# Sheet1.net
KiCad netlist of a schematic drawn in Altium Designer
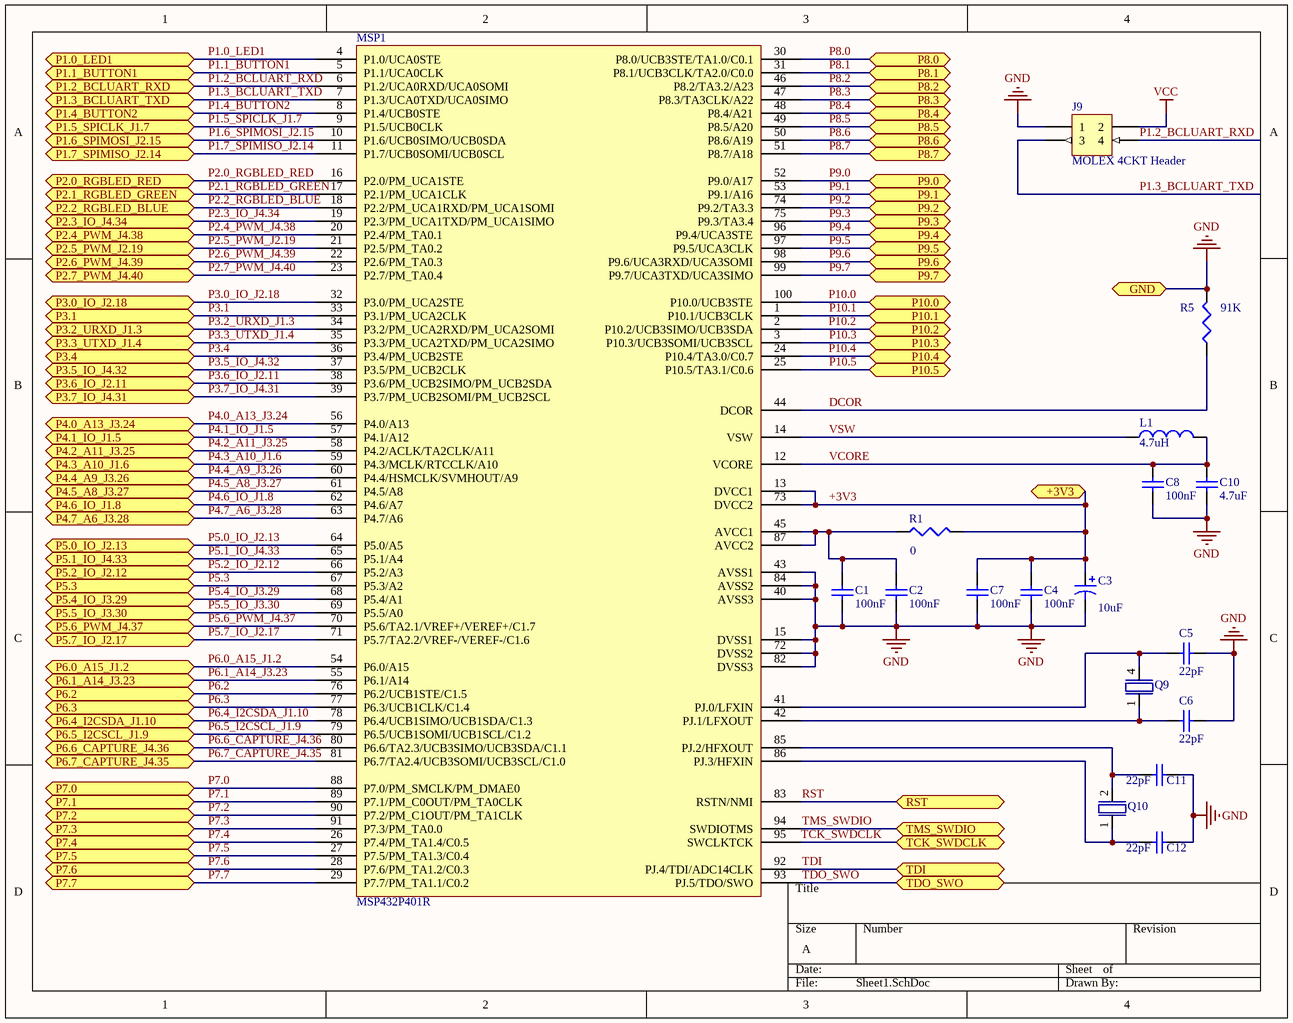
[diagram p0: Sheet1.SchDoc]

(export (version "E")
  (design (tool "Eeschema 10.0.6"))
  (components
    (comp (ref "C1")
      (value "100nF")
      (footprint "0402")
      (description "Capacitor (Semiconductor SIM Model)")
      (fields (field (name "Comment") "Cap Semi") (field (name "PUBLISHER") "Altium Limited"))
      (libsource (lib "Miscellaneous Devices") (part "Cap Semi"))
    )
    (comp (ref "C2")
      (value "100nF")
      (footprint "0402")
      (description "Capacitor (Semiconductor SIM Model)")
      (fields (field (name "Comment") "Cap Semi") (field (name "PUBLISHER") "Altium Limited"))
      (libsource (lib "Miscellaneous Devices") (part "Cap Semi"))
    )
    (comp (ref "C3")
      (value "10uF")
      (footprint "C0805")
      (description "Polarized Capacitor (Surface Mount)")
      (fields (field (name "Comment") "Cap Pol3") (field (name "PUBLISHER") "Altium Limited"))
      (libsource (lib "Miscellaneous Devices") (part "Cap Pol3"))
    )
    (comp (ref "C4")
      (value "100nF")
      (footprint "0402")
      (description "Capacitor (Semiconductor SIM Model)")
      (fields (field (name "Comment") "Cap Semi") (field (name "PUBLISHER") "Altium Limited"))
      (libsource (lib "Miscellaneous Devices") (part "Cap Semi"))
    )
    (comp (ref "C5")
      (value "22pF")
      (footprint "0402")
      (description "Capacitor (Semiconductor SIM Model)")
      (fields (field (name "Comment") "Cap Semi") (field (name "PUBLISHER") "Altium Limited"))
      (libsource (lib "Miscellaneous Devices") (part "Cap Semi"))
    )
    (comp (ref "C6")
      (value "22pF")
      (footprint "0402")
      (description "Capacitor (Semiconductor SIM Model)")
      (fields (field (name "Comment") "Cap Semi") (field (name "PUBLISHER") "Altium Limited"))
      (libsource (lib "Miscellaneous Devices") (part "Cap Semi"))
    )
    (comp (ref "C7")
      (value "100nF")
      (footprint "0402")
      (description "Capacitor (Semiconductor SIM Model)")
      (fields (field (name "Comment") "Cap Semi") (field (name "PUBLISHER") "Altium Limited"))
      (libsource (lib "Miscellaneous Devices") (part "Cap Semi"))
    )
    (comp (ref "C8")
      (value "100nF")
      (footprint "0402")
      (description "Capacitor (Semiconductor SIM Model)")
      (fields (field (name "Comment") "Cap Semi") (field (name "PUBLISHER") "Altium Limited"))
      (libsource (lib "Miscellaneous Devices") (part "Cap Semi"))
    )
    (comp (ref "C10")
      (value "4.7uF")
      (footprint "0402")
      (description "Capacitor (Semiconductor SIM Model)")
      (fields (field (name "Comment") "Cap Semi") (field (name "PUBLISHER") "Altium Limited"))
      (libsource (lib "Miscellaneous Devices") (part "Cap Semi"))
    )
    (comp (ref "C11")
      (value "22pF")
      (footprint "0402")
      (description "Capacitor (Semiconductor SIM Model)")
      (fields (field (name "Comment") "Cap Semi") (field (name "PUBLISHER") "Altium Limited"))
      (libsource (lib "Miscellaneous Devices") (part "Cap Semi"))
    )
    (comp (ref "C12")
      (value "22pF")
      (footprint "0402")
      (description "Capacitor (Semiconductor SIM Model)")
      (fields (field (name "Comment") "Cap Semi") (field (name "PUBLISHER") "Altium Limited"))
      (libsource (lib "Miscellaneous Devices") (part "Cap Semi"))
    )
    (comp (ref "J9")
      (value "MOLEX 4CKT Header")
      (footprint "MOLEX 4CKT Header")
      (libsource (lib "actuatorBoard") (part "MOLEX 4CKT Header"))
    )
    (comp (ref "L1")
      (value "4.7uH")
      (footprint "0402-A")
      (description "Inductor")
      (fields (field (name "PUBLISHER") "Altium Limited"))
      (libsource (lib "Miscellaneous Devices") (part "Inductor"))
    )
    (comp (ref "MSP1")
      (value "MSP432P401R")
      (footprint "MSP432P401R")
      (libsource (lib "actuatorBoard") (part "MSP432P401R"))
    )
    (comp (ref "Q9")
      (value "Crystal Oscillator")
      (footprint "4-SOJ")
      (libsource (lib "actuatorBoard") (part "Crystal Oscillator"))
    )
    (comp (ref "Q10")
      (value "Crystal Oscillator")
      (footprint "HC-49/US")
      (libsource (lib "") (part "Crystal Oscillator_1"))
    )
    (comp (ref "R1")
      (value "0")
      (footprint "J1-0603")
      (description "Resistor")
      (fields (field (name "Comment") "Res3") (field (name "PUBLISHER") "Altium Limited"))
      (libsource (lib "Miscellaneous Devices") (part "Res3"))
    )
    (comp (ref "R5")
      (value "91K")
      (footprint "J1-0603")
      (description "Resistor")
      (fields (field (name "Comment") "Res3") (field (name "PUBLISHER") "Altium Limited"))
      (libsource (lib "Miscellaneous Devices") (part "Res3"))
    )
  )
  (nets
    (net (code "1") (name "/+3V3") (class "Default")
      (node (ref "C3") (pin "1") (pinfunction "1_1") (pintype "passive"))
      (node (ref "C4") (pin "2") (pinfunction "2_2") (pintype "passive"))
      (node (ref "C7") (pin "2") (pinfunction "2_2") (pintype "passive"))
      (node (ref "MSP1") (pin "13") (pinfunction "DVCC1_13") (pintype "passive"))
      (node (ref "MSP1") (pin "73") (pinfunction "DVCC2_73") (pintype "passive"))
      (node (ref "R1") (pin "2") (pinfunction "2_2") (pintype "passive"))
    )
    (net (code "2") (name "/DCOR") (class "Default")
      (node (ref "MSP1") (pin "44") (pinfunction "DCOR_44") (pintype "passive"))
      (node (ref "R5") (pin "1") (pinfunction "1_1") (pintype "passive"))
    )
    (net (code "3") (name "/P1.0_LED1") (class "Default")
      (node (ref "MSP1") (pin "4") (pinfunction "P1.0/UCA0STE_4") (pintype "passive"))
    )
    (net (code "4") (name "/P1.1_BUTTON1") (class "Default")
      (node (ref "MSP1") (pin "5") (pinfunction "P1.1/UCA0CLK_5") (pintype "passive"))
    )
    (net (code "5") (name "/P1.2_BCLUART_RXD") (class "Default")
      (node (ref "J9") (pin "4") (pinfunction "4_4") (pintype "input"))
      (node (ref "MSP1") (pin "6") (pinfunction "P1.2/UCA0RXD/UCA0SOMI_6") (pintype "passive"))
    )
    (net (code "6") (name "/P1.3_BCLUART_TXD") (class "Default")
      (node (ref "J9") (pin "3") (pinfunction "3_3") (pintype "output"))
      (node (ref "MSP1") (pin "7") (pinfunction "P1.3/UCA0TXD/UCA0SIMO_7") (pintype "passive"))
    )
    (net (code "7") (name "/P1.4_BUTTON2") (class "Default")
      (node (ref "MSP1") (pin "8") (pinfunction "P1.4/UCB0STE_8") (pintype "passive"))
    )
    (net (code "8") (name "/P1.5_SPICLK_J1.7") (class "Default")
      (node (ref "MSP1") (pin "9") (pinfunction "P1.5/UCB0CLK_9") (pintype "passive"))
    )
    (net (code "9") (name "/P1.6_SPIMOSI_J2.15") (class "Default")
      (node (ref "MSP1") (pin "10") (pinfunction "P1.6/UCB0SIMO/UCB0SDA_10") (pintype "passive"))
    )
    (net (code "10") (name "/P1.7_SPIMISO_J2.14") (class "Default")
      (node (ref "MSP1") (pin "11") (pinfunction "P1.7/UCB0SOMI/UCB0SCL_11") (pintype "passive"))
    )
    (net (code "11") (name "/P2.0_RGBLED_RED") (class "Default")
      (node (ref "MSP1") (pin "16") (pinfunction "P2.0/PM_UCA1STE_16") (pintype "passive"))
    )
    (net (code "12") (name "/P2.1_RGBLED_GREEN") (class "Default")
      (node (ref "MSP1") (pin "17") (pinfunction "P2.1/PM_UCA1CLK_17") (pintype "passive"))
    )
    (net (code "13") (name "/P2.2_RGBLED_BLUE") (class "Default")
      (node (ref "MSP1") (pin "18") (pinfunction "P2.2/PM_UCA1RXD/PM_UCA1SOMI_18") (pintype "passive"))
    )
    (net (code "14") (name "/P2.3_IO_J4.34") (class "Default")
      (node (ref "MSP1") (pin "19") (pinfunction "P2.3/PM_UCA1TXD/PM_UCA1SIMO_19") (pintype "passive"))
    )
    (net (code "15") (name "/P2.4_PWM_J4.38") (class "Default")
      (node (ref "MSP1") (pin "20") (pinfunction "P2.4/PM_TA0.1_20") (pintype "passive"))
    )
    (net (code "16") (name "/P2.5_PWM_J2.19") (class "Default")
      (node (ref "MSP1") (pin "21") (pinfunction "P2.5/PM_TA0.2_21") (pintype "passive"))
    )
    (net (code "17") (name "/P2.6_PWM_J4.39") (class "Default")
      (node (ref "MSP1") (pin "22") (pinfunction "P2.6/PM_TA0.3_22") (pintype "passive"))
    )
    (net (code "18") (name "/P2.7_PWM_J4.40") (class "Default")
      (node (ref "MSP1") (pin "23") (pinfunction "P2.7/PM_TA0.4_23") (pintype "passive"))
    )
    (net (code "19") (name "/P3.0_IO_J2.18") (class "Default")
      (node (ref "MSP1") (pin "32") (pinfunction "P3.0/PM_UCA2STE_32") (pintype "passive"))
    )
    (net (code "20") (name "/P3.1") (class "Default")
      (node (ref "MSP1") (pin "33") (pinfunction "P3.1/PM_UCA2CLK_33") (pintype "passive"))
    )
    (net (code "21") (name "/P3.2_URXD_J1.3") (class "Default")
      (node (ref "MSP1") (pin "34") (pinfunction "P3.2/PM_UCA2RXD/PM_UCA2SOMI_34") (pintype "passive"))
    )
    (net (code "22") (name "/P3.3_UTXD_J1.4") (class "Default")
      (node (ref "MSP1") (pin "35") (pinfunction "P3.3/PM_UCA2TXD/PM_UCA2SIMO_35") (pintype "passive"))
    )
    (net (code "23") (name "/P3.4") (class "Default")
      (node (ref "MSP1") (pin "36") (pinfunction "P3.4/PM_UCB2STE_36") (pintype "passive"))
    )
    (net (code "24") (name "/P3.5_IO_J4.32") (class "Default")
      (node (ref "MSP1") (pin "37") (pinfunction "P3.5/PM_UCB2CLK_37") (pintype "passive"))
    )
    (net (code "25") (name "/P3.6_IO_J2.11") (class "Default")
      (node (ref "MSP1") (pin "38") (pinfunction "P3.6/PM_UCB2SIMO/PM_UCB2SDA_38") (pintype "passive"))
    )
    (net (code "26") (name "/P3.7_IO_J4.31") (class "Default")
      (node (ref "MSP1") (pin "39") (pinfunction "P3.7/PM_UCB2SOMI/PM_UCB2SCL_39") (pintype "passive"))
    )
    (net (code "27") (name "/P4.0_A13_J3.24") (class "Default")
      (node (ref "MSP1") (pin "56") (pinfunction "P4.0/A13_56") (pintype "passive"))
    )
    (net (code "28") (name "/P4.1_IO_J1.5") (class "Default")
      (node (ref "MSP1") (pin "57") (pinfunction "P4.1/A12_57") (pintype "passive"))
    )
    (net (code "29") (name "/P4.2_A11_J3.25") (class "Default")
      (node (ref "MSP1") (pin "58") (pinfunction "P4.2/ACLK/TA2CLK/A11_58") (pintype "passive"))
    )
    (net (code "30") (name "/P4.3_A10_J1.6") (class "Default")
      (node (ref "MSP1") (pin "59") (pinfunction "P4.3/MCLK/RTCCLK/A10_59") (pintype "passive"))
    )
    (net (code "31") (name "/P4.4_A9_J3.26") (class "Default")
      (node (ref "MSP1") (pin "60") (pinfunction "P4.4/HSMCLK/SVMHOUT/A9_60") (pintype "passive"))
    )
    (net (code "32") (name "/P4.5_A8_J3.27") (class "Default")
      (node (ref "MSP1") (pin "61") (pinfunction "P4.5/A8_61") (pintype "passive"))
    )
    (net (code "33") (name "/P4.6_IO_J1.8") (class "Default")
      (node (ref "MSP1") (pin "62") (pinfunction "P4.6/A7_62") (pintype "passive"))
    )
    (net (code "34") (name "/P4.7_A6_J3.28") (class "Default")
      (node (ref "MSP1") (pin "63") (pinfunction "P4.7/A6_63") (pintype "passive"))
    )
    (net (code "35") (name "/P5.0_IO_J2.13") (class "Default")
      (node (ref "MSP1") (pin "64") (pinfunction "P5.0/A5_64") (pintype "passive"))
    )
    (net (code "36") (name "/P5.1_IO_J4.33") (class "Default")
      (node (ref "MSP1") (pin "65") (pinfunction "P5.1/A4_65") (pintype "passive"))
    )
    (net (code "37") (name "/P5.2_IO_J2.12") (class "Default")
      (node (ref "MSP1") (pin "66") (pinfunction "P5.2/A3_66") (pintype "passive"))
    )
    (net (code "38") (name "/P5.3") (class "Default")
      (node (ref "MSP1") (pin "67") (pinfunction "P5.3/A2_67") (pintype "passive"))
    )
    (net (code "39") (name "/P5.4_IO_J3.29") (class "Default")
      (node (ref "MSP1") (pin "68") (pinfunction "P5.4/A1_68") (pintype "passive"))
    )
    (net (code "40") (name "/P5.5_IO_J3.30") (class "Default")
      (node (ref "MSP1") (pin "69") (pinfunction "P5.5/A0_69") (pintype "passive"))
    )
    (net (code "41") (name "/P5.6_PWM_J4.37") (class "Default")
      (node (ref "MSP1") (pin "70") (pinfunction "P5.6/TA2.1/VREF+/VEREF+/C1.7_70") (pintype "passive"))
    )
    (net (code "42") (name "/P5.7_IO_J2.17") (class "Default")
      (node (ref "MSP1") (pin "71") (pinfunction "P5.7/TA2.2/VREF-/VEREF-/C1.6_71") (pintype "passive"))
    )
    (net (code "43") (name "/P6.0_A15_J1.2") (class "Default")
      (node (ref "MSP1") (pin "54") (pinfunction "P6.0/A15_54") (pintype "passive"))
    )
    (net (code "44") (name "/P6.1_A14_J3.23") (class "Default")
      (node (ref "MSP1") (pin "55") (pinfunction "P6.1/A14_55") (pintype "passive"))
    )
    (net (code "45") (name "/P6.2") (class "Default")
      (node (ref "MSP1") (pin "76") (pinfunction "P6.2/UCB1STE/C1.5_76") (pintype "passive"))
    )
    (net (code "46") (name "/P6.3") (class "Default")
      (node (ref "MSP1") (pin "77") (pinfunction "P6.3/UCB1CLK/C1.4_77") (pintype "passive"))
    )
    (net (code "47") (name "/P6.4_I2CSDA_J1.10") (class "Default")
      (node (ref "MSP1") (pin "78") (pinfunction "P6.4/UCB1SIMO/UCB1SDA/C1.3_78") (pintype "passive"))
    )
    (net (code "48") (name "/P6.5_I2CSCL_J1.9") (class "Default")
      (node (ref "MSP1") (pin "79") (pinfunction "P6.5/UCB1SOMI/UCB1SCL/C1.2_79") (pintype "passive"))
    )
    (net (code "49") (name "/P6.6_CAPTURE_J4.36") (class "Default")
      (node (ref "MSP1") (pin "80") (pinfunction "P6.6/TA2.3/UCB3SIMO/UCB3SDA/C1.1_80") (pintype "passive"))
    )
    (net (code "50") (name "/P6.7_CAPTURE_J4.35") (class "Default")
      (node (ref "MSP1") (pin "81") (pinfunction "P6.7/TA2.4/UCB3SOMI/UCB3SCL/C1.0_81") (pintype "passive"))
    )
    (net (code "51") (name "/P7.0") (class "Default")
      (node (ref "MSP1") (pin "88") (pinfunction "P7.0/PM_SMCLK/PM_DMAE0_88") (pintype "passive"))
    )
    (net (code "52") (name "/P7.1") (class "Default")
      (node (ref "MSP1") (pin "89") (pinfunction "P7.1/PM_C0OUT/PM_TA0CLK_89") (pintype "passive"))
    )
    (net (code "53") (name "/P7.2") (class "Default")
      (node (ref "MSP1") (pin "90") (pinfunction "P7.2/PM_C1OUT/PM_TA1CLK_90") (pintype "passive"))
    )
    (net (code "54") (name "/P7.3") (class "Default")
      (node (ref "MSP1") (pin "91") (pinfunction "P7.3/PM_TA0.0_91") (pintype "passive"))
    )
    (net (code "55") (name "/P7.4") (class "Default")
      (node (ref "MSP1") (pin "26") (pinfunction "P7.4/PM_TA1.4/C0.5_26") (pintype "passive"))
    )
    (net (code "56") (name "/P7.5") (class "Default")
      (node (ref "MSP1") (pin "27") (pinfunction "P7.5/PM_TA1.3/C0.4_27") (pintype "passive"))
    )
    (net (code "57") (name "/P7.6") (class "Default")
      (node (ref "MSP1") (pin "28") (pinfunction "P7.6/PM_TA1.2/C0.3_28") (pintype "passive"))
    )
    (net (code "58") (name "/P7.7") (class "Default")
      (node (ref "MSP1") (pin "29") (pinfunction "P7.7/PM_TA1.1/C0.2_29") (pintype "passive"))
    )
    (net (code "59") (name "/P8.0") (class "Default")
      (node (ref "MSP1") (pin "30") (pinfunction "P8.0/UCB3STE/TA1.0/C0.1_30") (pintype "passive"))
    )
    (net (code "60") (name "/P8.1") (class "Default")
      (node (ref "MSP1") (pin "31") (pinfunction "P8.1/UCB3CLK/TA2.0/C0.0_31") (pintype "passive"))
    )
    (net (code "61") (name "/P8.2") (class "Default")
      (node (ref "MSP1") (pin "46") (pinfunction "P8.2/TA3.2/A23_46") (pintype "passive"))
    )
    (net (code "62") (name "/P8.3") (class "Default")
      (node (ref "MSP1") (pin "47") (pinfunction "P8.3/TA3CLK/A22_47") (pintype "passive"))
    )
    (net (code "63") (name "/P8.4") (class "Default")
      (node (ref "MSP1") (pin "48") (pinfunction "P8.4/A21_48") (pintype "passive"))
    )
    (net (code "64") (name "/P8.5") (class "Default")
      (node (ref "MSP1") (pin "49") (pinfunction "P8.5/A20_49") (pintype "passive"))
    )
    (net (code "65") (name "/P8.6") (class "Default")
      (node (ref "MSP1") (pin "50") (pinfunction "P8.6/A19_50") (pintype "passive"))
    )
    (net (code "66") (name "/P8.7") (class "Default")
      (node (ref "MSP1") (pin "51") (pinfunction "P8.7/A18_51") (pintype "passive"))
    )
    (net (code "67") (name "/P9.0") (class "Default")
      (node (ref "MSP1") (pin "52") (pinfunction "P9.0/A17_52") (pintype "passive"))
    )
    (net (code "68") (name "/P9.1") (class "Default")
      (node (ref "MSP1") (pin "53") (pinfunction "P9.1/A16_53") (pintype "passive"))
    )
    (net (code "69") (name "/P9.2") (class "Default")
      (node (ref "MSP1") (pin "74") (pinfunction "P9.2/TA3.3_74") (pintype "passive"))
    )
    (net (code "70") (name "/P9.3") (class "Default")
      (node (ref "MSP1") (pin "75") (pinfunction "P9.3/TA3.4_75") (pintype "passive"))
    )
    (net (code "71") (name "/P9.4") (class "Default")
      (node (ref "MSP1") (pin "96") (pinfunction "P9.4/UCA3STE_96") (pintype "passive"))
    )
    (net (code "72") (name "/P9.5") (class "Default")
      (node (ref "MSP1") (pin "97") (pinfunction "P9.5/UCA3CLK_97") (pintype "passive"))
    )
    (net (code "73") (name "/P9.6") (class "Default")
      (node (ref "MSP1") (pin "98") (pinfunction "P9.6/UCA3RXD/UCA3SOMI_98") (pintype "passive"))
    )
    (net (code "74") (name "/P9.7") (class "Default")
      (node (ref "MSP1") (pin "99") (pinfunction "P9.7/UCA3TXD/UCA3SIMO_99") (pintype "passive"))
    )
    (net (code "75") (name "/P10.0") (class "Default")
      (node (ref "MSP1") (pin "100") (pinfunction "P10.0/UCB3STE_100") (pintype "passive"))
    )
    (net (code "76") (name "/P10.1") (class "Default")
      (node (ref "MSP1") (pin "1") (pinfunction "P10.1/UCB3CLK_1") (pintype "passive"))
    )
    (net (code "77") (name "/P10.2") (class "Default")
      (node (ref "MSP1") (pin "2") (pinfunction "P10.2/UCB3SIMO/UCB3SDA_2") (pintype "passive"))
    )
    (net (code "78") (name "/P10.3") (class "Default")
      (node (ref "MSP1") (pin "3") (pinfunction "P10.3/UCB3SOMI/UCB3SCL_3") (pintype "passive"))
    )
    (net (code "79") (name "/P10.4") (class "Default")
      (node (ref "MSP1") (pin "24") (pinfunction "P10.4/TA3.0/C0.7_24") (pintype "passive"))
    )
    (net (code "80") (name "/P10.5") (class "Default")
      (node (ref "MSP1") (pin "25") (pinfunction "P10.5/TA3.1/C0.6_25") (pintype "passive"))
    )
    (net (code "81") (name "/RST") (class "Default")
      (node (ref "MSP1") (pin "83") (pinfunction "RSTN/NMI_83") (pintype "passive"))
    )
    (net (code "82") (name "/TCK_SWDCLK") (class "Default")
      (node (ref "MSP1") (pin "95") (pinfunction "SWCLKTCK_95") (pintype "passive"))
    )
    (net (code "83") (name "/TDI") (class "Default")
      (node (ref "MSP1") (pin "92") (pinfunction "PJ.4/TDI/ADC14CLK_92") (pintype "passive"))
    )
    (net (code "84") (name "/TDO_SWO") (class "Default")
      (node (ref "MSP1") (pin "93") (pinfunction "PJ.5/TDO/SWO_93") (pintype "passive"))
    )
    (net (code "85") (name "/TMS_SWDIO") (class "Default")
      (node (ref "MSP1") (pin "94") (pinfunction "SWDIOTMS_94") (pintype "passive"))
    )
    (net (code "86") (name "/VCORE") (class "Default")
      (node (ref "C10") (pin "2") (pinfunction "2_2") (pintype "passive"))
      (node (ref "C8") (pin "2") (pinfunction "2_2") (pintype "passive"))
      (node (ref "L1") (pin "2") (pinfunction "2_2") (pintype "passive"))
      (node (ref "MSP1") (pin "12") (pinfunction "VCORE_12") (pintype "passive"))
    )
    (net (code "87") (name "/VSW") (class "Default")
      (node (ref "L1") (pin "1") (pinfunction "1_1") (pintype "passive"))
      (node (ref "MSP1") (pin "14") (pinfunction "VSW_14") (pintype "passive"))
    )
    (net (code "88") (name "GND") (class "Default")
      (node (ref "C1") (pin "1") (pinfunction "1_1") (pintype "passive"))
      (node (ref "C10") (pin "1") (pinfunction "1_1") (pintype "passive"))
      (node (ref "C11") (pin "1") (pinfunction "1_1") (pintype "passive"))
      (node (ref "C12") (pin "1") (pinfunction "1_1") (pintype "passive"))
      (node (ref "C2") (pin "1") (pinfunction "1_1") (pintype "passive"))
      (node (ref "C3") (pin "2") (pinfunction "2_2") (pintype "passive"))
      (node (ref "C4") (pin "1") (pinfunction "1_1") (pintype "passive"))
      (node (ref "C5") (pin "1") (pinfunction "1_1") (pintype "passive"))
      (node (ref "C6") (pin "1") (pinfunction "1_1") (pintype "passive"))
      (node (ref "C7") (pin "1") (pinfunction "1_1") (pintype "passive"))
      (node (ref "C8") (pin "1") (pinfunction "1_1") (pintype "passive"))
      (node (ref "J9") (pin "1") (pinfunction "1_1") (pintype "power_in"))
      (node (ref "MSP1") (pin "15") (pinfunction "DVSS1_15") (pintype "passive"))
      (node (ref "MSP1") (pin "40") (pinfunction "AVSS3_40") (pintype "passive"))
      (node (ref "MSP1") (pin "43") (pinfunction "AVSS1_43") (pintype "passive"))
      (node (ref "MSP1") (pin "72") (pinfunction "DVSS2_72") (pintype "passive"))
      (node (ref "MSP1") (pin "82") (pinfunction "DVSS3_82") (pintype "passive"))
      (node (ref "MSP1") (pin "84") (pinfunction "AVSS2_84") (pintype "passive"))
      (node (ref "R5") (pin "2") (pinfunction "2_2") (pintype "passive"))
    )
    (net (code "89") (name "Net-(MSP1-AVCC1)") (class "Default")
      (node (ref "C1") (pin "2") (pinfunction "2_2") (pintype "passive"))
      (node (ref "C2") (pin "2") (pinfunction "2_2") (pintype "passive"))
      (node (ref "MSP1") (pin "45") (pinfunction "AVCC1_45") (pintype "passive"))
      (node (ref "MSP1") (pin "87") (pinfunction "AVCC2_87") (pintype "passive"))
      (node (ref "R1") (pin "1") (pinfunction "1_1") (pintype "passive"))
    )
    (net (code "90") (name "Net-(MSP1-PJ.0{slash}LFXIN)") (class "Default")
      (node (ref "C5") (pin "2") (pinfunction "2_2") (pintype "passive"))
      (node (ref "MSP1") (pin "41") (pinfunction "PJ.0/LFXIN_41") (pintype "passive"))
      (node (ref "Q9") (pin "4") (pinfunction "4_4") (pintype "passive"))
    )
    (net (code "91") (name "Net-(MSP1-PJ.1{slash}LFXOUT)") (class "Default")
      (node (ref "C6") (pin "2") (pinfunction "2_2") (pintype "passive"))
      (node (ref "MSP1") (pin "42") (pinfunction "PJ.1/LFXOUT_42") (pintype "passive"))
      (node (ref "Q9") (pin "1") (pinfunction "1_1") (pintype "passive"))
    )
    (net (code "92") (name "Net-(MSP1-PJ.2{slash}HFXOUT)") (class "Default")
      (node (ref "C11") (pin "2") (pinfunction "2_2") (pintype "passive"))
      (node (ref "MSP1") (pin "85") (pinfunction "PJ.2/HFXOUT_85") (pintype "passive"))
      (node (ref "Q10") (pin "2") (pinfunction "2_2") (pintype "passive"))
    )
    (net (code "93") (name "Net-(MSP1-PJ.3{slash}HFXIN)") (class "Default")
      (node (ref "C12") (pin "2") (pinfunction "2_2") (pintype "passive"))
      (node (ref "MSP1") (pin "86") (pinfunction "PJ.3/HFXIN_86") (pintype "passive"))
      (node (ref "Q10") (pin "1") (pinfunction "1_1") (pintype "passive"))
    )
    (net (code "94") (name "VCC") (class "Default")
      (node (ref "J9") (pin "2") (pinfunction "2_2") (pintype "power_in"))
    )
  )
)
